# NEURON_SCHEMATIC_EASYEDA.net
KiCad netlist of a schematic drawn in EasyEDA
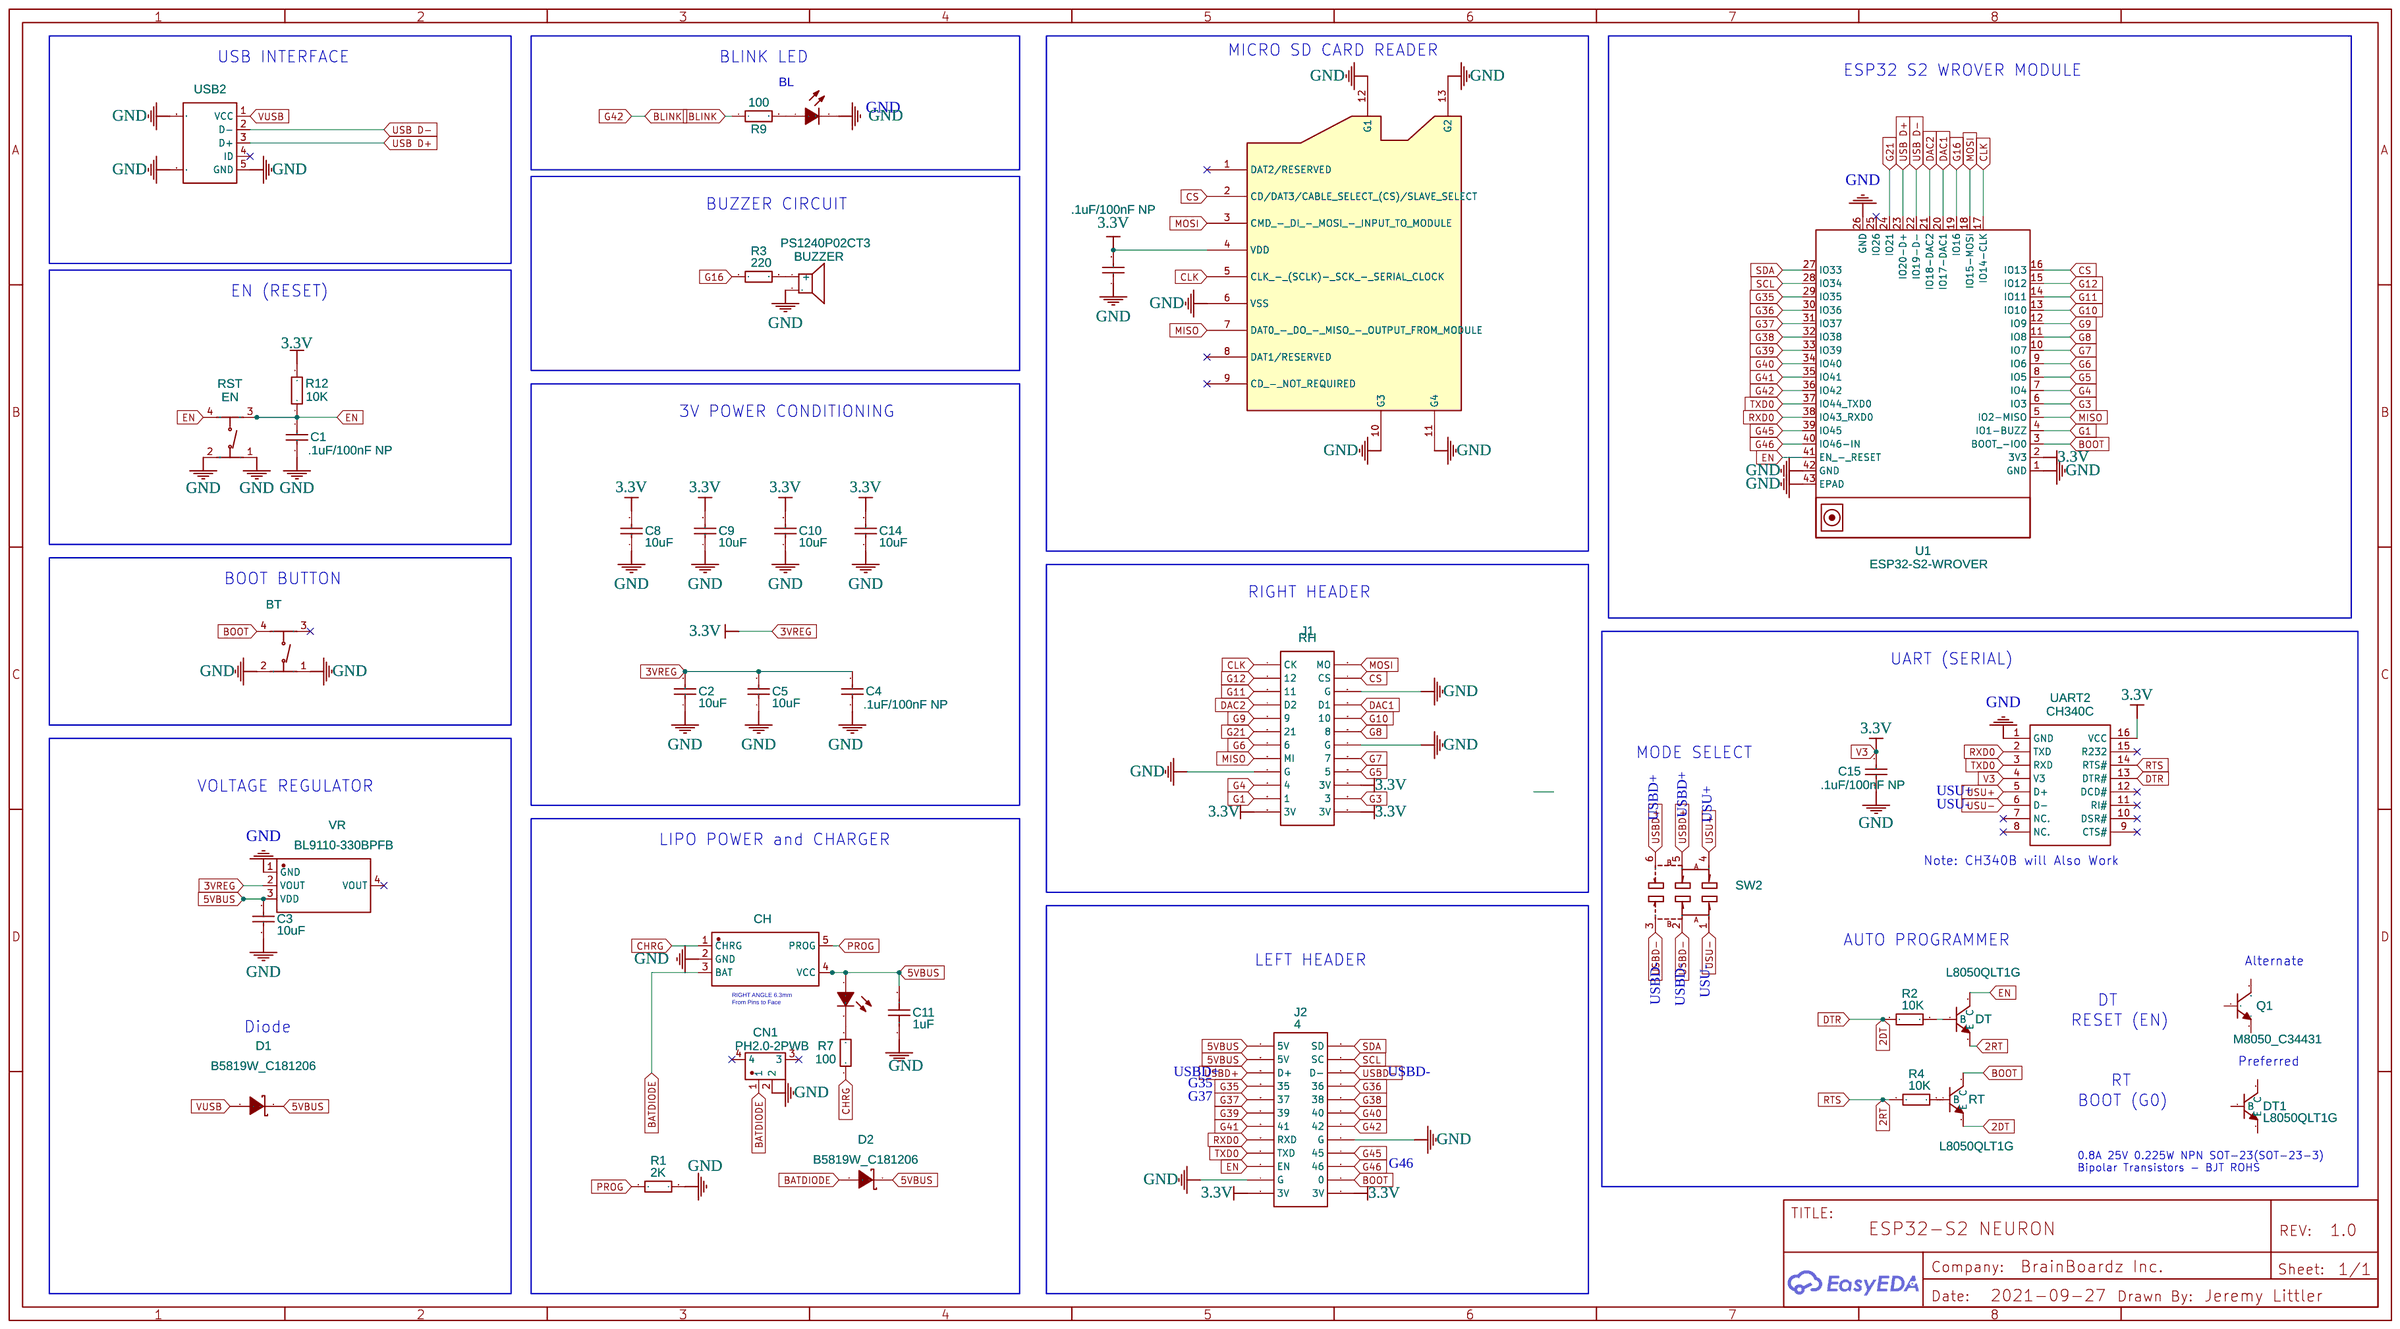
[diagram p0: schematic sheet]

(export (version "E")
  (design (tool "Eeschema 10.0.6"))
  (components
    (comp (ref "BLINK")
      (value "15-21SYGC/S530-E2/TR8")
      (fields (field (name "BOM_Supplier Part") "C73550"))
      (libsource (lib "") (part "15-21SYGC/S530-E2/TR8_1"))
    )
    (comp (ref "BT")
      (value "BOOT")
      (fields
        (field (name "BOM_Manufacturer Part") "TS-1187A-C-E-B")
        (field (name "BOM_Supplier Part") "C318887")
      )
      (libsource (lib "") (part "TS-1187A-C-E-B"))
    )
    (comp (ref "BUZZER")
      (value "PS1240P02CT3")
      (fields (field (name "BOM_Supplier Part") "C76873"))
      (libsource (lib "") (part "PS1240P02CT3"))
    )
    (comp (ref "C1")
      (value ".1uF/100nF NP")
      (fields
        (field (name "BOM_Manufacturer Part") "CL31B104KBCNNNC")
        (field (name "BOM_Supplier Part") "C24497")
      )
      (libsource (lib "") (part "CL31B104KBCNNNC_1"))
    )
    (comp (ref "C2")
      (value "10uF")
      (fields
        (field (name "BOM_Manufacturer Part") "CL31A106KBHNNNE")
        (field (name "BOM_Supplier Part") "C13585")
      )
      (libsource (lib "") (part "CL31A106KBHNNNE"))
    )
    (comp (ref "C3")
      (value "10uF")
      (fields
        (field (name "BOM_Manufacturer Part") "CL31A106KBHNNNE")
        (field (name "BOM_Supplier Part") "C13585")
      )
      (libsource (lib "") (part "CL31A106KBHNNNE"))
    )
    (comp (ref "C4")
      (value ".1uF/100nF NP")
      (fields
        (field (name "BOM_Manufacturer Part") "CL31B104KBCNNNC")
        (field (name "BOM_Supplier Part") "C24497")
      )
      (libsource (lib "") (part "CL31B104KBCNNNC_1"))
    )
    (comp (ref "C5")
      (value "10uF")
      (fields
        (field (name "BOM_Manufacturer Part") "CL31A106KBHNNNE")
        (field (name "BOM_Supplier Part") "C13585")
      )
      (libsource (lib "") (part "CL31A106KBHNNNE"))
    )
    (comp (ref "C8")
      (value "10uF")
      (fields
        (field (name "BOM_Manufacturer Part") "CL31A106KBHNNNE")
        (field (name "BOM_Supplier Part") "C13585")
      )
      (libsource (lib "") (part "CL31A106KBHNNNE"))
    )
    (comp (ref "C9")
      (value "10uF")
      (fields
        (field (name "BOM_Manufacturer Part") "CL31A106KBHNNNE")
        (field (name "BOM_Supplier Part") "C13585")
      )
      (libsource (lib "") (part "CL31A106KBHNNNE"))
    )
    (comp (ref "C10")
      (value "10uF")
      (fields
        (field (name "BOM_Manufacturer Part") "CL31A106KBHNNNE")
        (field (name "BOM_Supplier Part") "C13585")
      )
      (libsource (lib "") (part "CL31A106KBHNNNE"))
    )
    (comp (ref "C11")
      (value "1uF")
      (fields
        (field (name "BOM_Manufacturer Part") "CL31B105KBHNNNE")
        (field (name "BOM_Supplier Part") "C1848")
      )
      (libsource (lib "") (part "CL31B105KBHNNNE"))
    )
    (comp (ref "C13")
      (value ".1uF/100nF NP")
      (fields
        (field (name "BOM_Manufacturer Part") "CL31B104KBCNNNC")
        (field (name "BOM_Supplier Part") "C24497")
      )
      (libsource (lib "") (part "CL31B104KBCNNNC"))
    )
    (comp (ref "C14")
      (value "10uF")
      (fields
        (field (name "BOM_Manufacturer Part") "CL31A106KBHNNNE")
        (field (name "BOM_Supplier Part") "C13585")
      )
      (libsource (lib "") (part "CL31A106KBHNNNE"))
    )
    (comp (ref "C15")
      (value ".1uF/100nF NP")
      (fields
        (field (name "BOM_Manufacturer Part") "CL31B104KBCNNNC")
        (field (name "BOM_Supplier Part") "C24497")
      )
      (libsource (lib "") (part "CL31B104KBCNNNC"))
    )
    (comp (ref "CG")
      (value "15-21SYGC/S530-E2/TR8")
      (fields (field (name "BOM_Supplier Part") "C73550"))
      (libsource (lib "") (part "15-21SYGC/S530-E2/TR8"))
    )
    (comp (ref "CH")
      (value "CH")
      (fields (field (name "BOM_Manufacturer Part") "TP4054") (field (name "BOM_Supplier Part") "C32574"))
      (libsource (lib "") (part "TP4054"))
    )
    (comp (ref "CN1")
      (value "PH2.0-2PWB")
      (fields
        (field (name "BOM_Manufacturer Part") "PH2.0-2PWB Horizontal")
        (field (name "BOM_Supplier Part") "C47647")
      )
      (libsource (lib "") (part "PH2.0-2PWB"))
    )
    (comp (ref "D1")
      (value "B5819W_C181206")
      (fields (field (name "BOM_Manufacturer Part") "B5819W") (field (name "BOM_Supplier Part") "C181206"))
      (libsource (lib "") (part "B5819W_C181206"))
    )
    (comp (ref "D2")
      (value "B5819W_C181206")
      (fields (field (name "BOM_Manufacturer Part") "B5819W") (field (name "BOM_Supplier Part") "C181206"))
      (libsource (lib "") (part "B5819W_C181206"))
    )
    (comp (ref "DT")
      (value "L8050QLT1G")
      (fields (field (name "BOM_Supplier Part") "C49581"))
      (libsource (lib "") (part "L8050QLT1G"))
    )
    (comp (ref "DT1")
      (value "L8050QLT1G")
      (fields (field (name "BOM_Supplier Part") "C49581"))
      (libsource (lib "") (part "L8050QLT1G"))
    )
    (comp (ref "J1")
      (value "RH")
      (fields (field (name "BOM_Manufacturer Part") "New SchematicLib"))
      (libsource (lib "") (part "HDR 2.54mm 2x12"))
    )
    (comp (ref "J2")
      (value "4")
      (fields (field (name "BOM_Manufacturer Part") "New SchematicLib"))
      (libsource (lib "") (part "HDR 2.54mm 2x12_1"))
    )
    (comp (ref "MICROSD")
      (value "TF-15×15")
      (fields (field (name "BOM_Supplier Part") "C111196"))
      (libsource (lib "") (part "TF-15×15"))
    )
    (comp (ref "Q1")
      (value "M8050_C34431")
      (fields (field (name "BOM_Manufacturer Part") "M8050") (field (name "BOM_Supplier Part") "C34431"))
      (libsource (lib "") (part "M8050_C34431"))
    )
    (comp (ref "R1")
      (value "2K")
      (fields
        (field (name "BOM_Manufacturer Part") "1206W4F2001T5E")
        (field (name "BOM_Supplier Part") "C17944")
      )
      (libsource (lib "") (part "1206W4F2001T5E"))
    )
    (comp (ref "R2")
      (value "10K")
      (fields
        (field (name "BOM_Manufacturer Part") "AECR1206F10K0K9")
        (field (name "BOM_Supplier Part") "C328409")
      )
      (libsource (lib "") (part "AECR1206F10K0K9_1"))
    )
    (comp (ref "R3")
      (value "220")
      (fields
        (field (name "BOM_Manufacturer Part") "1206W4J0221T5E")
        (field (name "BOM_Supplier Part") "C25363")
      )
      (libsource (lib "") (part "1206W4J0221T5E"))
    )
    (comp (ref "R4")
      (value "10K")
      (fields
        (field (name "BOM_Manufacturer Part") "AECR1206F10K0K9")
        (field (name "BOM_Supplier Part") "C328409")
      )
      (libsource (lib "") (part "AECR1206F10K0K9_1"))
    )
    (comp (ref "R7")
      (value "100")
      (fields
        (field (name "BOM_Manufacturer Part") "1206W4F1000T5E")
        (field (name "BOM_Supplier Part") "C17901")
      )
      (libsource (lib "") (part "1206W4F1000T5E"))
    )
    (comp (ref "R9")
      (value "100")
      (fields
        (field (name "BOM_Manufacturer Part") "1206W4F1000T5E")
        (field (name "BOM_Supplier Part") "C17901")
      )
      (libsource (lib "") (part "1206W4F1000T5E_1"))
    )
    (comp (ref "R12")
      (value "10K")
      (fields
        (field (name "BOM_Manufacturer Part") "AECR1206F10K0K9")
        (field (name "BOM_Supplier Part") "C328409")
      )
      (libsource (lib "") (part "AECR1206F10K0K9"))
    )
    (comp (ref "RST")
      (value "EN")
      (fields
        (field (name "BOM_Manufacturer Part") "TS-1187A-C-E-B")
        (field (name "BOM_Supplier Part") "C318887")
      )
      (libsource (lib "") (part "TS-1187A-C-E-B_1"))
    )
    (comp (ref "RT")
      (value "L8050QLT1G")
      (fields (field (name "BOM_Supplier Part") "C49581"))
      (libsource (lib "") (part "L8050QLT1G_1"))
    )
    (comp (ref "SW2")
      (value "K2-2235D-F1")
      (fields (field (name "BOM_Supplier Part") "C108742"))
      (libsource (lib "") (part "K2-2235D-F1"))
    )
    (comp (ref "U1")
      (value "ESP32-S2-WROVER")
      (fields (field (name "BOM_Manufacturer Part") "ESP32-S2-WROVER-I"))
      (libsource (lib "") (part "ESP32-S2-WROVER-I"))
    )
    (comp (ref "UART2")
      (value "CH340C")
      (fields (field (name "BOM_Supplier Part") "C84681"))
      (libsource (lib "") (part "CH340C"))
    )
    (comp (ref "USB2")
      (value "Mini USB-B 5P-Female-TH_C46398")
      (fields
        (field (name "BOM_Manufacturer Part") "MINI 5PFemale90Degree plate four feet copper shell LCPVinyl")
        (field (name "BOM_Supplier Part") "C46398")
      )
      (libsource (lib "") (part "Mini USB-B 5P-Female-TH_C46398"))
    )
    (comp (ref "VR")
      (value "BL9110-330BPFB")
      (fields (field (name "BOM_Supplier Part") "C169246"))
      (libsource (lib "") (part "BL9110-330BPFB"))
    )
  )
  (nets
    (net (code "1") (name "2DT") (class "Default")
      (node (ref "R2") (pin "2") (pinfunction "2_2") (pintype "unspecified"))
      (node (ref "RT") (pin "2") (pinfunction "E_2") (pintype "unspecified"))
      (node (ref "UART2") (pin "13") (pinfunction "DTR#_13") (pintype "unspecified"))
    )
    (net (code "2") (name "2RT") (class "Default")
      (node (ref "DT") (pin "2") (pinfunction "E_2") (pintype "unspecified"))
      (node (ref "R4") (pin "2") (pinfunction "2_2") (pintype "unspecified"))
      (node (ref "UART2") (pin "14") (pinfunction "RTS#_14") (pintype "unspecified"))
    )
    (net (code "3") (name "3VREG") (class "Default")
      (node (ref "C10") (pin "2") (pinfunction "2_2") (pintype "input"))
      (node (ref "C13") (pin "2") (pinfunction "2_2") (pintype "input"))
      (node (ref "C14") (pin "2") (pinfunction "2_2") (pintype "input"))
      (node (ref "C15") (pin "2") (pinfunction "2_2") (pintype "input"))
      (node (ref "C2") (pin "2") (pinfunction "2_2") (pintype "input"))
      (node (ref "C4") (pin "1") (pinfunction "1_1") (pintype "input"))
      (node (ref "C5") (pin "2") (pinfunction "2_2") (pintype "input"))
      (node (ref "C8") (pin "2") (pinfunction "2_2") (pintype "input"))
      (node (ref "C9") (pin "2") (pinfunction "2_2") (pintype "input"))
      (node (ref "J1") (pin "20") (pinfunction "3V_20") (pintype "unspecified"))
      (node (ref "J1") (pin "23") (pinfunction "3V_23") (pintype "unspecified"))
      (node (ref "J1") (pin "24") (pinfunction "3V_24") (pintype "unspecified"))
      (node (ref "J2") (pin "1") (pinfunction "3V_1") (pintype "unspecified"))
      (node (ref "J2") (pin "2") (pinfunction "3V_2") (pintype "unspecified"))
      (node (ref "MICROSD") (pin "4") (pinfunction "VDD_4") (pintype "input"))
      (node (ref "R12") (pin "2") (pinfunction "2_2") (pintype "unspecified"))
      (node (ref "U1") (pin "2") (pinfunction "3V3_2") (pintype "unspecified"))
      (node (ref "UART2") (pin "16") (pinfunction "VCC_16") (pintype "unspecified"))
      (node (ref "UART2") (pin "4") (pinfunction "V3_4") (pintype "unspecified"))
      (node (ref "VR") (pin "2") (pinfunction "VOUT_2") (pintype "unspecified"))
    )
    (net (code "4") (name "5VBUS") (class "Default")
      (node (ref "C11") (pin "2") (pinfunction "2_2") (pintype "unspecified"))
      (node (ref "C3") (pin "2") (pinfunction "2_2") (pintype "input"))
      (node (ref "CG") (pin "1") (pinfunction "A_1") (pintype "input"))
      (node (ref "CH") (pin "4") (pinfunction "VCC_4") (pintype "unspecified"))
      (node (ref "D1") (pin "1") (pinfunction "K_1") (pintype "unspecified"))
      (node (ref "D2") (pin "1") (pinfunction "K_1") (pintype "unspecified"))
      (node (ref "J2") (pin "22") (pinfunction "5V_22") (pintype "unspecified"))
      (node (ref "J2") (pin "24") (pinfunction "5V_24") (pintype "unspecified"))
      (node (ref "VR") (pin "3") (pinfunction "VDD_3") (pintype "unspecified"))
    )
    (net (code "5") (name "BATDIODE") (class "Default")
      (node (ref "CH") (pin "3") (pinfunction "BAT_3") (pintype "unspecified"))
      (node (ref "CN1") (pin "1") (pinfunction "1_1") (pintype "unspecified"))
      (node (ref "D2") (pin "2") (pinfunction "A_2") (pintype "unspecified"))
    )
    (net (code "6") (name "BLINK") (class "Default")
      (node (ref "J2") (pin "11") (pinfunction "42_11") (pintype "unspecified"))
      (node (ref "R9") (pin "1") (pinfunction "1_1") (pintype "input"))
      (node (ref "U1") (pin "36") (pinfunction "IO42_36") (pintype "unspecified"))
    )
    (net (code "7") (name "BOOT") (class "Default")
      (node (ref "BT") (pin "4") (pinfunction "D_4") (pintype "unspecified"))
      (node (ref "J2") (pin "3") (pinfunction "0_3") (pintype "unspecified"))
      (node (ref "RT") (pin "3") (pinfunction "C_3") (pintype "unspecified"))
      (node (ref "U1") (pin "3") (pinfunction "BOOT_-IO0_3") (pintype "unspecified"))
    )
    (net (code "8") (name "CHRG") (class "Default")
      (node (ref "CH") (pin "1") (pinfunction "CHRG_1") (pintype "unspecified"))
      (node (ref "R7") (pin "1") (pinfunction "1_1") (pintype "input"))
    )
    (net (code "9") (name "CLK") (class "Default")
      (node (ref "J1") (pin "1") (pinfunction "CK_1") (pintype "unspecified"))
      (node (ref "MICROSD") (pin "5") (pinfunction "CLK_-_(SCLK)-_SCK_-_SERIAL_CLOCK_5") (pintype "input"))
      (node (ref "U1") (pin "17") (pinfunction "IO14-CLK_17") (pintype "unspecified"))
    )
    (net (code "10") (name "CS") (class "Default")
      (node (ref "J1") (pin "4") (pinfunction "CS_4") (pintype "unspecified"))
      (node (ref "MICROSD") (pin "2") (pinfunction "CD/DAT3/CABLE_SELECT_(CS)/SLAVE_SELECT_2") (pintype "input"))
      (node (ref "U1") (pin "16") (pinfunction "IO13_16") (pintype "unspecified"))
    )
    (net (code "11") (name "DAC1") (class "Default")
      (node (ref "J1") (pin "8") (pinfunction "D1_8") (pintype "unspecified"))
      (node (ref "U1") (pin "20") (pinfunction "IO17-DAC1_20") (pintype "unspecified"))
    )
    (net (code "12") (name "DAC2") (class "Default")
      (node (ref "J1") (pin "7") (pinfunction "D2_7") (pintype "unspecified"))
      (node (ref "U1") (pin "21") (pinfunction "IO18-DAC2_21") (pintype "unspecified"))
    )
    (net (code "13") (name "EN") (class "Default")
      (node (ref "C1") (pin "1") (pinfunction "1_1") (pintype "input"))
      (node (ref "DT") (pin "3") (pinfunction "C_3") (pintype "unspecified"))
      (node (ref "J2") (pin "6") (pinfunction "EN_6") (pintype "unspecified"))
      (node (ref "R12") (pin "1") (pinfunction "1_1") (pintype "unspecified"))
      (node (ref "RST") (pin "3") (pinfunction "C_3") (pintype "unspecified"))
      (node (ref "RST") (pin "4") (pinfunction "D_4") (pintype "unspecified"))
      (node (ref "U1") (pin "41") (pinfunction "EN_-_RESET_41") (pintype "unspecified"))
    )
    (net (code "14") (name "G1") (class "Default")
      (node (ref "J1") (pin "21") (pinfunction "1_21") (pintype "unspecified"))
      (node (ref "U1") (pin "4") (pinfunction "IO1-BUZZ_4") (pintype "unspecified"))
    )
    (net (code "15") (name "G3") (class "Default")
      (node (ref "J1") (pin "22") (pinfunction "3_22") (pintype "unspecified"))
      (node (ref "U1") (pin "6") (pinfunction "IO3_6") (pintype "unspecified"))
    )
    (net (code "16") (name "G4") (class "Default")
      (node (ref "J1") (pin "19") (pinfunction "4_19") (pintype "unspecified"))
      (node (ref "U1") (pin "7") (pinfunction "IO4_7") (pintype "unspecified"))
    )
    (net (code "17") (name "G5") (class "Default")
      (node (ref "J1") (pin "18") (pinfunction "5_18") (pintype "unspecified"))
      (node (ref "U1") (pin "8") (pinfunction "IO5_8") (pintype "unspecified"))
    )
    (net (code "18") (name "G6") (class "Default")
      (node (ref "J1") (pin "13") (pinfunction "6_13") (pintype "unspecified"))
      (node (ref "U1") (pin "9") (pinfunction "IO6_9") (pintype "unspecified"))
    )
    (net (code "19") (name "G7") (class "Default")
      (node (ref "J1") (pin "16") (pinfunction "7_16") (pintype "unspecified"))
      (node (ref "U1") (pin "10") (pinfunction "IO7_10") (pintype "unspecified"))
    )
    (net (code "20") (name "G8") (class "Default")
      (node (ref "J1") (pin "12") (pinfunction "8_12") (pintype "unspecified"))
      (node (ref "U1") (pin "11") (pinfunction "IO8_11") (pintype "unspecified"))
    )
    (net (code "21") (name "G9") (class "Default")
      (node (ref "J1") (pin "9") (pinfunction "9_9") (pintype "unspecified"))
      (node (ref "U1") (pin "12") (pinfunction "IO9_12") (pintype "unspecified"))
    )
    (net (code "22") (name "G10") (class "Default")
      (node (ref "J1") (pin "10") (pinfunction "10_10") (pintype "unspecified"))
      (node (ref "U1") (pin "13") (pinfunction "IO10_13") (pintype "unspecified"))
    )
    (net (code "23") (name "G11") (class "Default")
      (node (ref "J1") (pin "5") (pinfunction "11_5") (pintype "unspecified"))
      (node (ref "U1") (pin "14") (pinfunction "IO11_14") (pintype "unspecified"))
    )
    (net (code "24") (name "G12") (class "Default")
      (node (ref "J1") (pin "3") (pinfunction "12_3") (pintype "unspecified"))
      (node (ref "U1") (pin "15") (pinfunction "IO12_15") (pintype "unspecified"))
    )
    (net (code "25") (name "G16") (class "Default")
      (node (ref "R3") (pin "1") (pinfunction "1_1") (pintype "input"))
      (node (ref "U1") (pin "19") (pinfunction "IO16_19") (pintype "unspecified"))
    )
    (net (code "26") (name "G21") (class "Default")
      (node (ref "J1") (pin "11") (pinfunction "21_11") (pintype "unspecified"))
      (node (ref "U1") (pin "24") (pinfunction "IO21_24") (pintype "unspecified"))
    )
    (net (code "27") (name "G35") (class "Default")
      (node (ref "J2") (pin "18") (pinfunction "35_18") (pintype "unspecified"))
      (node (ref "U1") (pin "29") (pinfunction "IO35_29") (pintype "unspecified"))
    )
    (net (code "28") (name "G36") (class "Default")
      (node (ref "J2") (pin "17") (pinfunction "36_17") (pintype "unspecified"))
      (node (ref "U1") (pin "30") (pinfunction "IO36_30") (pintype "unspecified"))
    )
    (net (code "29") (name "G37") (class "Default")
      (node (ref "J2") (pin "16") (pinfunction "37_16") (pintype "unspecified"))
      (node (ref "U1") (pin "31") (pinfunction "IO37_31") (pintype "unspecified"))
    )
    (net (code "30") (name "G38") (class "Default")
      (node (ref "J2") (pin "15") (pinfunction "38_15") (pintype "unspecified"))
      (node (ref "U1") (pin "32") (pinfunction "IO38_32") (pintype "unspecified"))
    )
    (net (code "31") (name "G39") (class "Default")
      (node (ref "J2") (pin "14") (pinfunction "39_14") (pintype "unspecified"))
      (node (ref "U1") (pin "33") (pinfunction "IO39_33") (pintype "unspecified"))
    )
    (net (code "32") (name "G40") (class "Default")
      (node (ref "J2") (pin "13") (pinfunction "40_13") (pintype "unspecified"))
      (node (ref "U1") (pin "34") (pinfunction "IO40_34") (pintype "unspecified"))
    )
    (net (code "33") (name "G41") (class "Default")
      (node (ref "J2") (pin "12") (pinfunction "41_12") (pintype "unspecified"))
      (node (ref "U1") (pin "35") (pinfunction "IO41_35") (pintype "unspecified"))
    )
    (net (code "34") (name "G45") (class "Default")
      (node (ref "J2") (pin "7") (pinfunction "45_7") (pintype "unspecified"))
      (node (ref "U1") (pin "39") (pinfunction "IO45_39") (pintype "unspecified"))
    )
    (net (code "35") (name "G46") (class "Default")
      (node (ref "J2") (pin "5") (pinfunction "46_5") (pintype "unspecified"))
      (node (ref "U1") (pin "40") (pinfunction "IO46-IN_40") (pintype "unspecified"))
    )
    (net (code "36") (name "GND") (class "Default")
      (node (ref "BLINK") (pin "2") (pinfunction "C_2") (pintype "input"))
      (node (ref "BT") (pin "1") (pinfunction "A_1") (pintype "unspecified"))
      (node (ref "BT") (pin "2") (pinfunction "B_2") (pintype "unspecified"))
      (node (ref "BUZZER") (pin "2") (pinfunction "2_2") (pintype "unspecified"))
      (node (ref "C1") (pin "2") (pinfunction "2_2") (pintype "input"))
      (node (ref "C10") (pin "1") (pinfunction "1_1") (pintype "input"))
      (node (ref "C11") (pin "1") (pinfunction "1_1") (pintype "unspecified"))
      (node (ref "C13") (pin "1") (pinfunction "1_1") (pintype "input"))
      (node (ref "C14") (pin "1") (pinfunction "1_1") (pintype "input"))
      (node (ref "C15") (pin "1") (pinfunction "1_1") (pintype "input"))
      (node (ref "C2") (pin "1") (pinfunction "1_1") (pintype "input"))
      (node (ref "C3") (pin "1") (pinfunction "1_1") (pintype "input"))
      (node (ref "C4") (pin "2") (pinfunction "2_2") (pintype "input"))
      (node (ref "C5") (pin "1") (pinfunction "1_1") (pintype "input"))
      (node (ref "C8") (pin "1") (pinfunction "1_1") (pintype "input"))
      (node (ref "C9") (pin "1") (pinfunction "1_1") (pintype "input"))
      (node (ref "CH") (pin "2") (pinfunction "GND_2") (pintype "unspecified"))
      (node (ref "CN1") (pin "2") (pinfunction "2_2") (pintype "unspecified"))
      (node (ref "J1") (pin "14") (pinfunction "G_14") (pintype "unspecified"))
      (node (ref "J1") (pin "17") (pinfunction "G_17") (pintype "unspecified"))
      (node (ref "J1") (pin "6") (pinfunction "G_6") (pintype "unspecified"))
      (node (ref "J2") (pin "4") (pinfunction "G_4") (pintype "unspecified"))
      (node (ref "J2") (pin "9") (pinfunction "G_9") (pintype "unspecified"))
      (node (ref "MICROSD") (pin "10") (pinfunction "G3_10") (pintype "input"))
      (node (ref "MICROSD") (pin "11") (pinfunction "G4_11") (pintype "input"))
      (node (ref "MICROSD") (pin "12") (pinfunction "G1_12") (pintype "input"))
      (node (ref "MICROSD") (pin "13") (pinfunction "G2_13") (pintype "input"))
      (node (ref "MICROSD") (pin "6") (pinfunction "VSS_6") (pintype "input"))
      (node (ref "R1") (pin "2") (pinfunction "2_2") (pintype "input"))
      (node (ref "RST") (pin "1") (pinfunction "A_1") (pintype "unspecified"))
      (node (ref "RST") (pin "2") (pinfunction "B_2") (pintype "unspecified"))
      (node (ref "U1") (pin "1") (pinfunction "GND_1") (pintype "unspecified"))
      (node (ref "U1") (pin "26") (pinfunction "GND_26") (pintype "unspecified"))
      (node (ref "U1") (pin "42") (pinfunction "GND_42") (pintype "unspecified"))
      (node (ref "U1") (pin "43") (pinfunction "EPAD_43") (pintype "unspecified"))
      (node (ref "UART2") (pin "1") (pinfunction "GND_1") (pintype "unspecified"))
      (node (ref "USB2") (pin "0") (pinfunction "0_0") (pintype "unspecified"))
      (node (ref "USB2") (pin "5") (pinfunction "GND_5") (pintype "input"))
      (node (ref "VR") (pin "1") (pinfunction "GND_1") (pintype "unspecified"))
    )
    (net (code "37") (name "MISO") (class "Default")
      (node (ref "J1") (pin "15") (pinfunction "MI_15") (pintype "unspecified"))
      (node (ref "MICROSD") (pin "7") (pinfunction "DAT0_-_DO_-_MISO_-_OUTPUT_FROM_MODULE_7") (pintype "input"))
      (node (ref "U1") (pin "5") (pinfunction "IO2-MISO_5") (pintype "unspecified"))
    )
    (net (code "38") (name "MOSI") (class "Default")
      (node (ref "J1") (pin "2") (pinfunction "MO_2") (pintype "unspecified"))
      (node (ref "MICROSD") (pin "3") (pinfunction "CMD_-_DI_-_MOSI_-_INPUT_TO_MODULE_3") (pintype "input"))
      (node (ref "U1") (pin "18") (pinfunction "IO15-MOSI_18") (pintype "unspecified"))
    )
    (net (code "39") (name "Net-(BLINK-A)") (class "Default")
      (node (ref "BLINK") (pin "1") (pinfunction "A_1") (pintype "input"))
      (node (ref "R9") (pin "2") (pinfunction "2_2") (pintype "input"))
    )
    (net (code "40") (name "Net-(BUZZER-+)") (class "Default")
      (node (ref "BUZZER") (pin "1") (pinfunction "+_1") (pintype "unspecified"))
      (node (ref "R3") (pin "2") (pinfunction "2_2") (pintype "input"))
    )
    (net (code "41") (name "Net-(CG-C)") (class "Default")
      (node (ref "CG") (pin "2") (pinfunction "C_2") (pintype "input"))
      (node (ref "R7") (pin "2") (pinfunction "2_2") (pintype "input"))
    )
    (net (code "42") (name "Net-(DT-B)") (class "Default")
      (node (ref "DT") (pin "1") (pinfunction "B_1") (pintype "unspecified"))
      (node (ref "R2") (pin "1") (pinfunction "1_1") (pintype "unspecified"))
    )
    (net (code "43") (name "PROG") (class "Default")
      (node (ref "CH") (pin "5") (pinfunction "PROG_5") (pintype "unspecified"))
      (node (ref "R1") (pin "1") (pinfunction "1_1") (pintype "input"))
    )
    (net (code "44") (name "RXD0") (class "Default")
      (node (ref "J2") (pin "10") (pinfunction "RXD_10") (pintype "unspecified"))
      (node (ref "U1") (pin "38") (pinfunction "IO43_RXD0_38") (pintype "unspecified"))
      (node (ref "UART2") (pin "2") (pinfunction "TXD_2") (pintype "unspecified"))
    )
    (net (code "45") (name "SCL") (class "Default")
      (node (ref "J2") (pin "21") (pinfunction "SC_21") (pintype "unspecified"))
      (node (ref "U1") (pin "28") (pinfunction "IO34_28") (pintype "unspecified"))
    )
    (net (code "46") (name "SDA") (class "Default")
      (node (ref "J2") (pin "23") (pinfunction "SD_23") (pintype "unspecified"))
      (node (ref "U1") (pin "27") (pinfunction "IO33_27") (pintype "unspecified"))
    )
    (net (code "47") (name "TXD0") (class "Default")
      (node (ref "J2") (pin "8") (pinfunction "TXD_8") (pintype "unspecified"))
      (node (ref "U1") (pin "37") (pinfunction "IO44_TXD0_37") (pintype "unspecified"))
      (node (ref "UART2") (pin "3") (pinfunction "RXD_3") (pintype "unspecified"))
    )
    (net (code "48") (name "USB D+") (class "Default")
      (node (ref "U1") (pin "23") (pinfunction "IO20-D+_23") (pintype "unspecified"))
      (node (ref "USB2") (pin "3") (pinfunction "D+_3") (pintype "input"))
    )
    (net (code "49") (name "USB D-") (class "Default")
      (node (ref "U1") (pin "22") (pinfunction "IO19-D-_22") (pintype "unspecified"))
      (node (ref "USB2") (pin "2") (pinfunction "D-_2") (pintype "input"))
    )
    (net (code "50") (name "USBD+") (class "Default")
      (node (ref "J2") (pin "20") (pinfunction "D+_20") (pintype "unspecified"))
      (node (ref "SW2") (pin "5") (pinfunction "5_5") (pintype "unspecified"))
      (node (ref "SW2") (pin "6") (pinfunction "6_6") (pintype "unspecified"))
    )
    (net (code "51") (name "USBD-") (class "Default")
      (node (ref "J2") (pin "19") (pinfunction "D-_19") (pintype "unspecified"))
      (node (ref "SW2") (pin "2") (pinfunction "2_2") (pintype "unspecified"))
      (node (ref "SW2") (pin "3") (pinfunction "3_3") (pintype "unspecified"))
    )
    (net (code "52") (name "USU+") (class "Default")
      (node (ref "SW2") (pin "4") (pinfunction "4_4") (pintype "unspecified"))
      (node (ref "UART2") (pin "5") (pinfunction "D+_5") (pintype "unspecified"))
    )
    (net (code "53") (name "USU-") (class "Default")
      (node (ref "SW2") (pin "1") (pinfunction "1_1") (pintype "unspecified"))
      (node (ref "UART2") (pin "6") (pinfunction "D-_6") (pintype "unspecified"))
    )
    (net (code "54") (name "VUSB") (class "Default")
      (node (ref "D1") (pin "2") (pinfunction "A_2") (pintype "unspecified"))
      (node (ref "USB2") (pin "1") (pinfunction "VCC_1") (pintype "input"))
    )
    (net (code "55") (name "unconnected-(BT-C-Pad3)") (class "Default")
      (node (ref "BT") (pin "3") (pinfunction "C_3") (pintype "unspecified+no_connect"))
    )
    (net (code "56") (name "unconnected-(CN1-Pad3)") (class "Default")
      (node (ref "CN1") (pin "3") (pinfunction "3_3") (pintype "unspecified+no_connect"))
    )
    (net (code "57") (name "unconnected-(CN1-Pad4)") (class "Default")
      (node (ref "CN1") (pin "4") (pinfunction "4_4") (pintype "unspecified+no_connect"))
    )
    (net (code "58") (name "unconnected-(DT1-B-Pad1)") (class "Default")
      (node (ref "DT1") (pin "1") (pinfunction "B_1") (pintype "unspecified"))
    )
    (net (code "59") (name "unconnected-(DT1-C-Pad3)") (class "Default")
      (node (ref "DT1") (pin "3") (pinfunction "C_3") (pintype "unspecified"))
    )
    (net (code "60") (name "unconnected-(DT1-E-Pad2)") (class "Default")
      (node (ref "DT1") (pin "2") (pinfunction "E_2") (pintype "unspecified"))
    )
    (net (code "61") (name "unconnected-(MICROSD-CD_-_NOT_REQUIRED-Pad9)") (class "Default")
      (node (ref "MICROSD") (pin "9") (pinfunction "CD_-_NOT_REQUIRED_9") (pintype "input+no_connect"))
    )
    (net (code "62") (name "unconnected-(MICROSD-DAT1{slash}RESERVED-Pad8)") (class "Default")
      (node (ref "MICROSD") (pin "8") (pinfunction "DAT1/RESERVED_8") (pintype "input+no_connect"))
    )
    (net (code "63") (name "unconnected-(MICROSD-DAT2{slash}RESERVED-Pad1)") (class "Default")
      (node (ref "MICROSD") (pin "1") (pinfunction "DAT2/RESERVED_1") (pintype "input+no_connect"))
    )
    (net (code "64") (name "unconnected-(Q1-B-Pad1)") (class "Default")
      (node (ref "Q1") (pin "1") (pinfunction "B_1") (pintype "unspecified"))
    )
    (net (code "65") (name "unconnected-(Q1-C-Pad3)") (class "Default")
      (node (ref "Q1") (pin "3") (pinfunction "C_3") (pintype "unspecified"))
    )
    (net (code "66") (name "unconnected-(Q1-E-Pad2)") (class "Default")
      (node (ref "Q1") (pin "2") (pinfunction "E_2") (pintype "unspecified"))
    )
    (net (code "67") (name "unconnected-(R4-Pad1)") (class "Default")
      (node (ref "R4") (pin "1") (pinfunction "1_1") (pintype "unspecified"))
    )
    (net (code "68") (name "unconnected-(RT-B-Pad1)") (class "Default")
      (node (ref "RT") (pin "1") (pinfunction "B_1") (pintype "unspecified"))
    )
    (net (code "69") (name "unconnected-(U1-IO26-Pad25)") (class "Default")
      (node (ref "U1") (pin "25") (pinfunction "IO26_25") (pintype "unspecified+no_connect"))
    )
    (net (code "70") (name "unconnected-(UART2-CTS#-Pad9)") (class "Default")
      (node (ref "UART2") (pin "9") (pinfunction "CTS#_9") (pintype "unspecified+no_connect"))
    )
    (net (code "71") (name "unconnected-(UART2-DCD#-Pad12)") (class "Default")
      (node (ref "UART2") (pin "12") (pinfunction "DCD#_12") (pintype "unspecified+no_connect"))
    )
    (net (code "72") (name "unconnected-(UART2-DSR#-Pad10)") (class "Default")
      (node (ref "UART2") (pin "10") (pinfunction "DSR#_10") (pintype "unspecified+no_connect"))
    )
    (net (code "73") (name "unconnected-(UART2-NC.-Pad7)") (class "Default")
      (node (ref "UART2") (pin "7") (pinfunction "NC._7") (pintype "unspecified+no_connect"))
    )
    (net (code "74") (name "unconnected-(UART2-NC.-Pad8)") (class "Default")
      (node (ref "UART2") (pin "8") (pinfunction "NC._8") (pintype "unspecified+no_connect"))
    )
    (net (code "75") (name "unconnected-(UART2-R232-Pad15)") (class "Default")
      (node (ref "UART2") (pin "15") (pinfunction "R232_15") (pintype "unspecified+no_connect"))
    )
    (net (code "76") (name "unconnected-(UART2-RI#-Pad11)") (class "Default")
      (node (ref "UART2") (pin "11") (pinfunction "RI#_11") (pintype "unspecified+no_connect"))
    )
    (net (code "77") (name "unconnected-(USB2-ID-Pad4)") (class "Default")
      (node (ref "USB2") (pin "4") (pinfunction "ID_4") (pintype "input+no_connect"))
    )
    (net (code "78") (name "unconnected-(VR-VOUT-Pad4)") (class "Default")
      (node (ref "VR") (pin "4") (pinfunction "VOUT_4") (pintype "unspecified+no_connect"))
    )
  )
)
